# GSM_LED_Indicators.net
KiCad netlist of a schematic drawn in Altium Designer
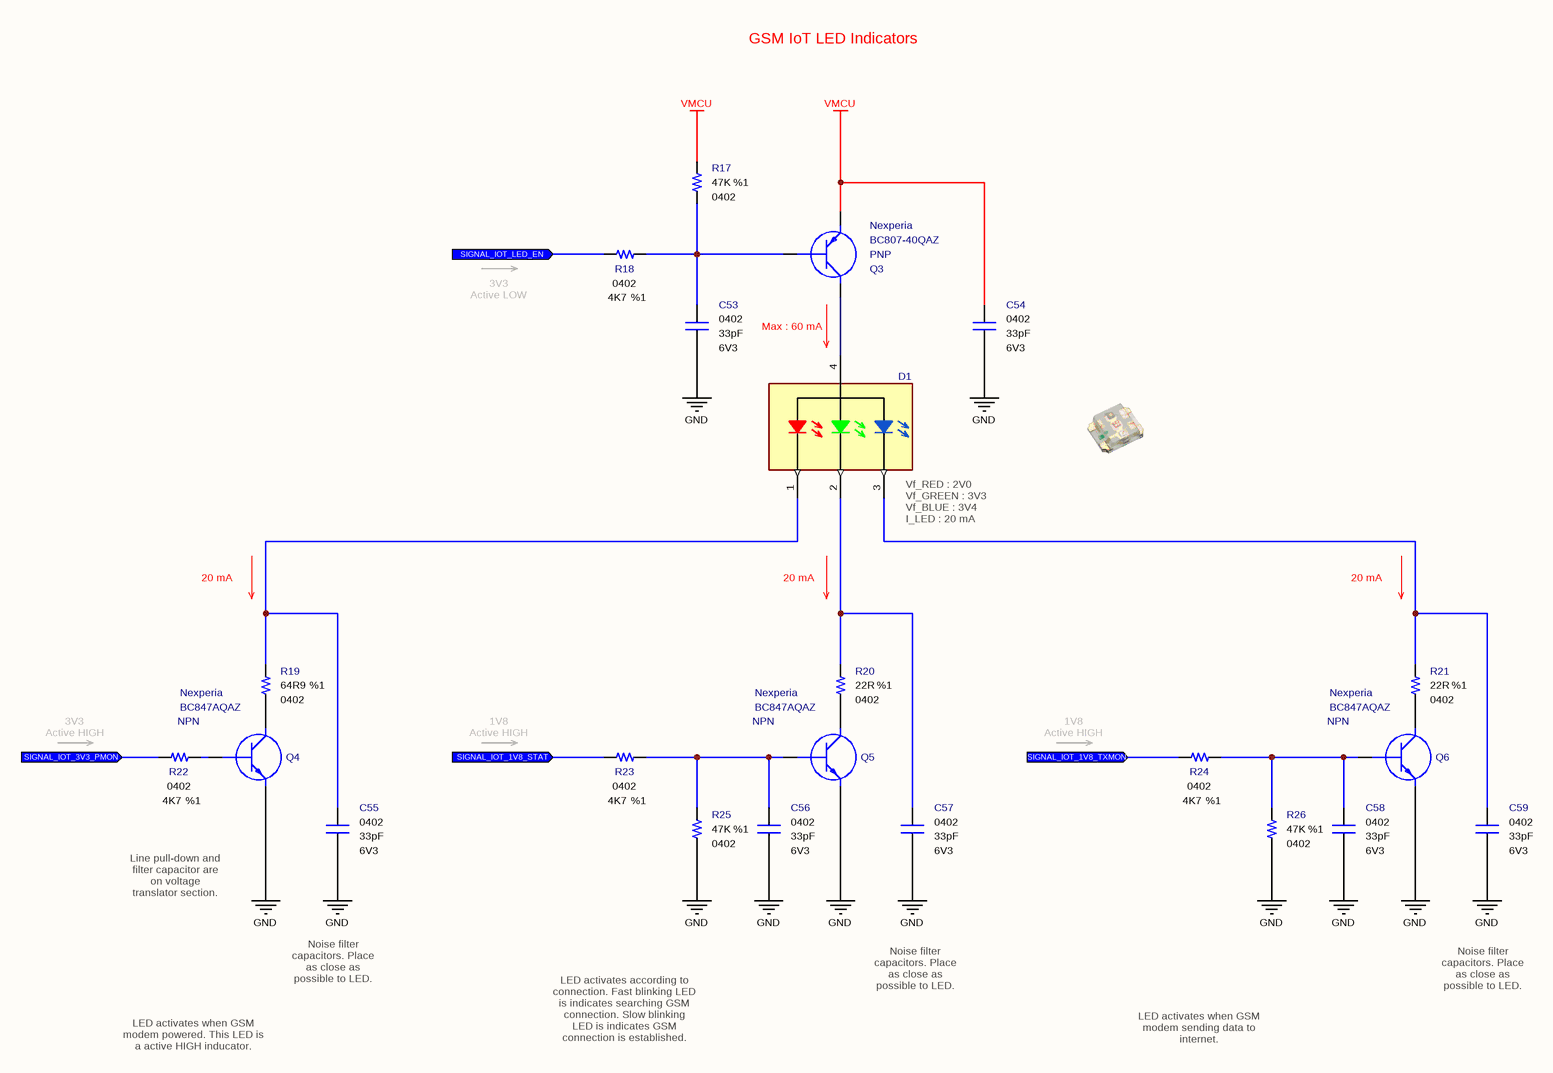
[diagram p0: GSM LED Indicators.SchDoc]

(export (version "E")
  (design (tool "Eeschema 10.0.6"))
  (components
    (comp (ref "C53")
      (value "33pF")
      (footprint "CAPACITOR_0402")
      (description "Capacitor - 33pF [0402] (Ceramic)")
      (fields
        (field (name "CASE") "0402")
        (field (name "TOLERANCE") "10%")
        (field (name "VOLTAGE") "6V3")
        (field (name "MANUFACTURER PART NUMBER") "C0402C330J9RACAUTO")
      )
      (libsource (lib "Ovoo_Library") (part "Capacitor - 33pF [0402-6V3]"))
    )
    (comp (ref "C54")
      (value "33pF")
      (footprint "CAPACITOR_0402")
      (description "Capacitor - 33pF [0402] (Ceramic)")
      (fields
        (field (name "CASE") "0402")
        (field (name "TOLERANCE") "10%")
        (field (name "VOLTAGE") "6V3")
        (field (name "MANUFACTURER PART NUMBER") "C0402C330J9RACAUTO")
      )
      (libsource (lib "Ovoo_Library") (part "Capacitor - 33pF [0402-6V3]"))
    )
    (comp (ref "C55")
      (value "33pF")
      (footprint "CAPACITOR_0402")
      (description "Capacitor - 33pF [0402] (Ceramic)")
      (fields
        (field (name "CASE") "0402")
        (field (name "TOLERANCE") "10%")
        (field (name "VOLTAGE") "6V3")
        (field (name "MANUFACTURER PART NUMBER") "C0402C330J9RACAUTO")
      )
      (libsource (lib "Ovoo_Library") (part "Capacitor - 33pF [0402-6V3]"))
    )
    (comp (ref "C56")
      (value "33pF")
      (footprint "CAPACITOR_0402")
      (description "Capacitor - 33pF [0402] (Ceramic)")
      (fields
        (field (name "CASE") "0402")
        (field (name "TOLERANCE") "10%")
        (field (name "VOLTAGE") "6V3")
        (field (name "MANUFACTURER PART NUMBER") "C0402C330J9RACAUTO")
      )
      (libsource (lib "Ovoo_Library") (part "Capacitor - 33pF [0402-6V3]"))
    )
    (comp (ref "C57")
      (value "33pF")
      (footprint "CAPACITOR_0402")
      (description "Capacitor - 33pF [0402] (Ceramic)")
      (fields
        (field (name "CASE") "0402")
        (field (name "TOLERANCE") "10%")
        (field (name "VOLTAGE") "6V3")
        (field (name "MANUFACTURER PART NUMBER") "C0402C330J9RACAUTO")
      )
      (libsource (lib "Ovoo_Library") (part "Capacitor - 33pF [0402-6V3]"))
    )
    (comp (ref "C58")
      (value "33pF")
      (footprint "CAPACITOR_0402")
      (description "Capacitor - 33pF [0402] (Ceramic)")
      (fields
        (field (name "CASE") "0402")
        (field (name "TOLERANCE") "10%")
        (field (name "VOLTAGE") "6V3")
        (field (name "MANUFACTURER PART NUMBER") "C0402C330J9RACAUTO")
      )
      (libsource (lib "Ovoo_Library") (part "Capacitor - 33pF [0402-6V3]"))
    )
    (comp (ref "C59")
      (value "33pF")
      (footprint "CAPACITOR_0402")
      (description "Capacitor - 33pF [0402] (Ceramic)")
      (fields
        (field (name "CASE") "0402")
        (field (name "TOLERANCE") "10%")
        (field (name "VOLTAGE") "6V3")
        (field (name "MANUFACTURER PART NUMBER") "C0402C330J9RACAUTO")
      )
      (libsource (lib "Ovoo_Library") (part "Capacitor - 33pF [0402-6V3]"))
    )
    (comp (ref "D1")
      (value "150066M153000")
      (footprint "Wurth_0606")
      (description "Standard LEDs - SMD PICOLED series Red LED")
      (fields (field (name "MOUSER PART NUMBER") "710-150066M153000"))
      (libsource (lib "Ovoo_Library") (part "Diode - RGB LED (150066M153000)"))
    )
    (comp (ref "Q3")
      (value "Bipolar PNP Transistors")
      (footprint "SOT1215")
      (description "Bipolar Transistors - BJT 45 V, 500 mA PNP gen purpose transistors")
      (fields
        (field (name "MOUSER PART NUMBER") "771-BC807-40QAZ")
        (field (name "POLARITY") "PNP")
        (field (name "MANUFACTURER NAME") "Nexperia")
        (field (name "MANUFACTURER PART NUMBER") "BC807-40QAZ")
      )
      (libsource (lib "Ovoo_Library") (part "Transistor - BC807"))
    )
    (comp (ref "Q4")
      (value "BC847AQAZ")
      (footprint "SOT1215")
      (description "Bipolar NPN Transistors")
      (fields
        (field (name "POLARITY") "NPN")
        (field (name "MANUFACTURER NAME") "Nexperia")
        (field (name "MANUFACTURER PART NUMBER") "BC847AQAZ")
      )
      (libsource (lib "Ovoo_Library") (part "Transistor - BC847"))
    )
    (comp (ref "Q5")
      (value "BC847AQAZ")
      (footprint "SOT1215")
      (description "Bipolar NPN Transistors")
      (fields
        (field (name "POLARITY") "NPN")
        (field (name "MANUFACTURER NAME") "Nexperia")
        (field (name "MANUFACTURER PART NUMBER") "BC847AQAZ")
      )
      (libsource (lib "Ovoo_Library") (part "Transistor - BC847"))
    )
    (comp (ref "Q6")
      (value "BC847AQAZ")
      (footprint "SOT1215")
      (description "Bipolar NPN Transistors")
      (fields
        (field (name "POLARITY") "NPN")
        (field (name "MANUFACTURER NAME") "Nexperia")
        (field (name "MANUFACTURER PART NUMBER") "BC847AQAZ")
      )
      (libsource (lib "Ovoo_Library") (part "Transistor - BC847"))
    )
    (comp (ref "R17")
      (value "47K")
      (footprint "RESISTOR_0402")
      (description "Thick Film Resistors - SMD 1/16 W 47 Kohms 1%")
      (fields
        (field (name "TOLERANCE") "%1")
        (field (name "CASE") "0402")
        (field (name "MANUFACTURER PART NUMBER") "CRCW040247K0FKED")
        (field (name "Comment") "47K - 0402 - %1 - 1/16W")
      )
      (libsource (lib "Ovoo_Library") (part "Resistor - 47K"))
    )
    (comp (ref "R18")
      (value "4K7")
      (footprint "RESISTOR_0402")
      (description "Thick Film Resistors - SMD 1/16 W 4.7 Kohms 1%")
      (fields
        (field (name "MANUFACTURER PART NUMBER") "CRCW04024K70FKED")
        (field (name "MOUSER PART NUMBER") "71-CRCW0402-4.7K-E3")
        (field (name "TOLERANCE") "%1")
        (field (name "CASE") "0402")
      )
      (libsource (lib "Ovoo_Library") (part "Resistor - 4K7"))
    )
    (comp (ref "R19")
      (value "64R9")
      (footprint "RESISTOR_0402")
      (description "Thick Film Resistors - SMD 1/16 W 64R9 Ohms 1%")
      (fields
        (field (name "MANUFACTURER PART NUMBER") "CRCW040264R9FKED")
        (field (name "MOUSER PART NUMBER") "71-CRCW0402-64.9-E3")
        (field (name "TOLERANCE") "%1")
        (field (name "CASE") "0402")
      )
      (libsource (lib "Ovoo_Library") (part "Resistor - 64R9"))
    )
    (comp (ref "R20")
      (value "22R")
      (footprint "RESISTOR_0402")
      (description "Thick Film Resistors - SMD 1/16 W 22R Ohms 1%")
      (fields
        (field (name "MANUFACTURER PART NUMBER") "CRCW040222R0FKED")
        (field (name "MOUSER PART NUMBER") "71-CRCW0402-22-E3")
        (field (name "TOLERANCE") "%1")
        (field (name "CASE") "0402")
      )
      (libsource (lib "Ovoo_Library") (part "Resistor - 22R"))
    )
    (comp (ref "R21")
      (value "22R")
      (footprint "RESISTOR_0402")
      (description "Thick Film Resistors - SMD 1/16 W 22R Ohms 1%")
      (fields
        (field (name "MANUFACTURER PART NUMBER") "CRCW040222R0FKED")
        (field (name "MOUSER PART NUMBER") "71-CRCW0402-22-E3")
        (field (name "TOLERANCE") "%1")
        (field (name "CASE") "0402")
      )
      (libsource (lib "Ovoo_Library") (part "Resistor - 22R"))
    )
    (comp (ref "R22")
      (value "4K7")
      (footprint "RESISTOR_0402")
      (description "Thick Film Resistors - SMD 1/16 W 4.7 Kohms 1%")
      (fields
        (field (name "MANUFACTURER PART NUMBER") "CRCW04024K70FKED")
        (field (name "MOUSER PART NUMBER") "71-CRCW0402-4.7K-E3")
        (field (name "TOLERANCE") "%1")
        (field (name "CASE") "0402")
      )
      (libsource (lib "Ovoo_Library") (part "Resistor - 4K7"))
    )
    (comp (ref "R23")
      (value "4K7")
      (footprint "RESISTOR_0402")
      (description "Thick Film Resistors - SMD 1/16 W 4.7 Kohms 1%")
      (fields
        (field (name "MANUFACTURER PART NUMBER") "CRCW04024K70FKED")
        (field (name "MOUSER PART NUMBER") "71-CRCW0402-4.7K-E3")
        (field (name "TOLERANCE") "%1")
        (field (name "CASE") "0402")
      )
      (libsource (lib "Ovoo_Library") (part "Resistor - 4K7"))
    )
    (comp (ref "R24")
      (value "4K7")
      (footprint "RESISTOR_0402")
      (description "Thick Film Resistors - SMD 1/16 W 4.7 Kohms 1%")
      (fields
        (field (name "MANUFACTURER PART NUMBER") "CRCW04024K70FKED")
        (field (name "MOUSER PART NUMBER") "71-CRCW0402-4.7K-E3")
        (field (name "TOLERANCE") "%1")
        (field (name "CASE") "0402")
      )
      (libsource (lib "Ovoo_Library") (part "Resistor - 4K7"))
    )
    (comp (ref "R25")
      (value "47K")
      (footprint "RESISTOR_0402")
      (description "Thick Film Resistors - SMD 1/16 W 47 Kohms 1%")
      (fields
        (field (name "TOLERANCE") "%1")
        (field (name "CASE") "0402")
        (field (name "MANUFACTURER PART NUMBER") "CRCW040247K0FKED")
        (field (name "Comment") "47K - 0402 - %1 - 1/16W")
      )
      (libsource (lib "Ovoo_Library") (part "Resistor - 47K"))
    )
    (comp (ref "R26")
      (value "47K")
      (footprint "RESISTOR_0402")
      (description "Thick Film Resistors - SMD 1/16 W 47 Kohms 1%")
      (fields
        (field (name "TOLERANCE") "%1")
        (field (name "CASE") "0402")
        (field (name "MANUFACTURER PART NUMBER") "CRCW040247K0FKED")
        (field (name "Comment") "47K - 0402 - %1 - 1/16W")
      )
      (libsource (lib "Ovoo_Library") (part "Resistor - 47K"))
    )
  )
  (nets
    (net (code "1") (name "/SIGNAL_IOT_1V8_STAT") (class "Default")
      (node (ref "R23") (pin "2") (pinfunction "2_2") (pintype "passive"))
    )
    (net (code "2") (name "/SIGNAL_IOT_1V8_TXMON") (class "Default")
      (node (ref "R24") (pin "2") (pinfunction "2_2") (pintype "passive"))
    )
    (net (code "3") (name "/SIGNAL_IOT_3V3_PMON") (class "Default")
      (node (ref "R22") (pin "2") (pinfunction "2_2") (pintype "passive"))
    )
    (net (code "4") (name "/SIGNAL_IOT_LED_EN") (class "Default")
      (node (ref "R18") (pin "2") (pinfunction "2_2") (pintype "passive"))
    )
    (net (code "5") (name "GND") (class "Default")
      (node (ref "C53") (pin "2") (pinfunction "2_2") (pintype "passive"))
      (node (ref "C54") (pin "2") (pinfunction "2_2") (pintype "passive"))
      (node (ref "C55") (pin "2") (pinfunction "2_2") (pintype "passive"))
      (node (ref "C56") (pin "2") (pinfunction "2_2") (pintype "passive"))
      (node (ref "C57") (pin "2") (pinfunction "2_2") (pintype "passive"))
      (node (ref "C58") (pin "2") (pinfunction "2_2") (pintype "passive"))
      (node (ref "C59") (pin "2") (pinfunction "2_2") (pintype "passive"))
      (node (ref "Q4") (pin "2") (pinfunction "E_2") (pintype "passive"))
      (node (ref "Q5") (pin "2") (pinfunction "E_2") (pintype "passive"))
      (node (ref "Q6") (pin "2") (pinfunction "E_2") (pintype "passive"))
      (node (ref "R25") (pin "1") (pinfunction "1_1") (pintype "passive"))
      (node (ref "R26") (pin "1") (pinfunction "1_1") (pintype "passive"))
    )
    (net (code "6") (name "Net-(C55-Pad1)") (class "Default")
      (node (ref "C55") (pin "1") (pinfunction "1_1") (pintype "passive"))
      (node (ref "D1") (pin "1") (pinfunction "1_1") (pintype "output"))
      (node (ref "R19") (pin "2") (pinfunction "2_2") (pintype "passive"))
    )
    (net (code "7") (name "Net-(C57-Pad1)") (class "Default")
      (node (ref "C57") (pin "1") (pinfunction "1_1") (pintype "passive"))
      (node (ref "D1") (pin "2") (pinfunction "2_2") (pintype "output"))
      (node (ref "R20") (pin "2") (pinfunction "2_2") (pintype "passive"))
    )
    (net (code "8") (name "Net-(C59-Pad1)") (class "Default")
      (node (ref "C59") (pin "1") (pinfunction "1_1") (pintype "passive"))
      (node (ref "D1") (pin "3") (pinfunction "3_3") (pintype "output"))
      (node (ref "R21") (pin "2") (pinfunction "2_2") (pintype "passive"))
    )
    (net (code "9") (name "Net-(Q3-B)") (class "Default")
      (node (ref "C53") (pin "1") (pinfunction "1_1") (pintype "passive"))
      (node (ref "Q3") (pin "1") (pinfunction "B_1") (pintype "passive"))
      (node (ref "R17") (pin "1") (pinfunction "1_1") (pintype "passive"))
      (node (ref "R18") (pin "1") (pinfunction "1_1") (pintype "passive"))
    )
    (net (code "10") (name "Net-(Q3-C)") (class "Default")
      (node (ref "D1") (pin "4") (pinfunction "4_4") (pintype "power_in"))
      (node (ref "Q3") (pin "3") (pinfunction "C_3") (pintype "passive"))
    )
    (net (code "11") (name "Net-(Q4-B)") (class "Default")
      (node (ref "Q4") (pin "1") (pinfunction "B_1") (pintype "passive"))
      (node (ref "R22") (pin "1") (pinfunction "1_1") (pintype "passive"))
    )
    (net (code "12") (name "Net-(Q4-C)") (class "Default")
      (node (ref "Q4") (pin "3") (pinfunction "C_3") (pintype "passive"))
      (node (ref "R19") (pin "1") (pinfunction "1_1") (pintype "passive"))
    )
    (net (code "13") (name "Net-(Q5-B)") (class "Default")
      (node (ref "C56") (pin "1") (pinfunction "1_1") (pintype "passive"))
      (node (ref "Q5") (pin "1") (pinfunction "B_1") (pintype "passive"))
      (node (ref "R23") (pin "1") (pinfunction "1_1") (pintype "passive"))
      (node (ref "R25") (pin "2") (pinfunction "2_2") (pintype "passive"))
    )
    (net (code "14") (name "Net-(Q5-C)") (class "Default")
      (node (ref "Q5") (pin "3") (pinfunction "C_3") (pintype "passive"))
      (node (ref "R20") (pin "1") (pinfunction "1_1") (pintype "passive"))
    )
    (net (code "15") (name "Net-(Q6-B)") (class "Default")
      (node (ref "C58") (pin "1") (pinfunction "1_1") (pintype "passive"))
      (node (ref "Q6") (pin "1") (pinfunction "B_1") (pintype "passive"))
      (node (ref "R24") (pin "1") (pinfunction "1_1") (pintype "passive"))
      (node (ref "R26") (pin "2") (pinfunction "2_2") (pintype "passive"))
    )
    (net (code "16") (name "Net-(Q6-C)") (class "Default")
      (node (ref "Q6") (pin "3") (pinfunction "C_3") (pintype "passive"))
      (node (ref "R21") (pin "1") (pinfunction "1_1") (pintype "passive"))
    )
    (net (code "17") (name "VMCU") (class "Default")
      (node (ref "C54") (pin "1") (pinfunction "1_1") (pintype "passive"))
      (node (ref "Q3") (pin "2") (pinfunction "E_2") (pintype "passive"))
      (node (ref "R17") (pin "2") (pinfunction "2_2") (pintype "passive"))
    )
  )
)
